# ESP-Grow_OLED_Rev_A.net
KiCad netlist of a schematic drawn in Altium Designer
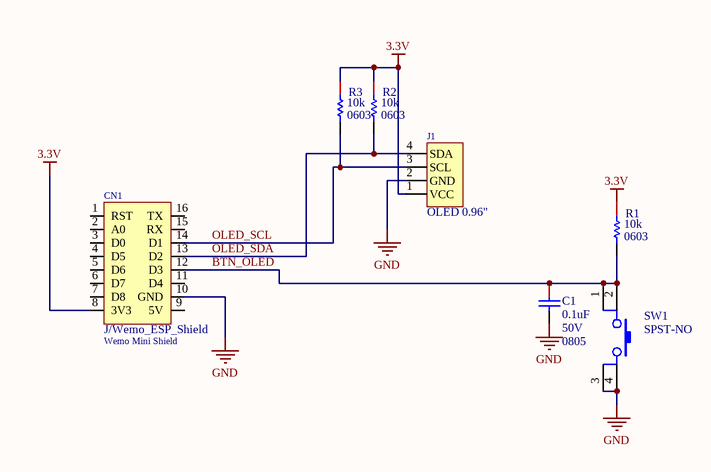
[diagram p0: ESP-Grow_OLED_Rev_A.SchDoc]

(export (version "E")
  (design (tool "Eeschema 10.0.6"))
  (components
    (comp (ref "C1")
      (value "0.1uF")
      (footprint "CAPC0805(2012)_L")
      (description "CAP CER 0.1UF 50V 10% X7R 0805")
      (fields
        (field (name "VOLTAGE (RATED)") "50V")
        (field (name "PACKAGE (IMPERIAL)") "0805")
        (field (name "TOLERANCE") "10%")
      )
      (libsource (lib "OLogic Nexus Vault") (part "=Capacitance"))
    )
    (comp (ref "CN1")
      (value "J/Wemo_ESP_Shield")
      (footprint "Wemos_d1")
      (description "Wemo Mini Shield for ESP-12")
      (fields (field (name "NAME") "Wemo Mini Shield"))
      (libsource (lib "Kyle_Lib_04-20-19") (part "J/Wemo_ESP_Shield"))
    )
    (comp (ref "J1")
      (value "OLED 0.96\"")
      (footprint "OLED_0.96_I2C")
      (description "SSD1306 I2C OLED 0.96\"")
      (libsource (lib "Kyle_Lib_04-20-19") (part "OLED_0.96_I2C"))
    )
    (comp (ref "R1")
      (value "10K")
      (footprint "RESC0603(1608)_M")
      (description "RES 10K OHM 1/10W 1% 0603 SMD")
      (fields
        (field (name "PACKAGE (IMPERIAL)") "0603")
        (field (name "RESISTANCE") "10k")
        (field (name "POWER") "100mW")
        (field (name "TOLERANCE") "1%")
      )
      (libsource (lib "OLogic Nexus Vault") (part "=Resistance"))
    )
    (comp (ref "R2")
      (value "10K")
      (footprint "RESC0603(1608)_M")
      (description "RES 10K OHM 1/10W 1% 0603 SMD")
      (fields
        (field (name "PACKAGE (IMPERIAL)") "0603")
        (field (name "RESISTANCE") "10k")
        (field (name "POWER") "100mW")
        (field (name "TOLERANCE") "1%")
      )
      (libsource (lib "OLogic Nexus Vault") (part "=Resistance"))
    )
    (comp (ref "R3")
      (value "10K")
      (footprint "RESC0603(1608)_M")
      (description "RES 10K OHM 1/10W 1% 0603 SMD")
      (fields
        (field (name "PACKAGE (IMPERIAL)") "0603")
        (field (name "RESISTANCE") "10k")
        (field (name "POWER") "100mW")
        (field (name "TOLERANCE") "1%")
      )
      (libsource (lib "OLogic Nexus Vault") (part "=Resistance"))
    )
    (comp (ref "SW1")
      (value "PTS645SM43SMTR92 LFS")
      (footprint "SW TACT Red 6mm x 6mm")
      (description "SWITCH TACTILE SPST-NO 0.05A 12V")
      (fields (field (name "CIRCUIT") "SPST-NO") (field (name "MANUFACTURER") "C&K"))
      (libsource (lib "altium-import") (part "root_0_PTS645SM43SMTR92 LFS_"))
    )
  )
  (nets
    (net (code "1") (name "/BTN_OLED") (class "Default")
      (node (ref "C1") (pin "1") (pinfunction "1_1") (pintype "passive"))
      (node (ref "CN1") (pin "12") (pinfunction "D3_12") (pintype "power_in"))
      (node (ref "R1") (pin "2") (pinfunction "2_2") (pintype "passive"))
      (node (ref "SW1") (pin "1") (pinfunction "1_1") (pintype "passive"))
      (node (ref "SW1") (pin "2") (pinfunction "2_2") (pintype "passive"))
    )
    (net (code "2") (name "/OLED_SCL") (class "Default")
      (node (ref "CN1") (pin "14") (pinfunction "D1_14") (pintype "power_in"))
      (node (ref "J1") (pin "3") (pinfunction "SCL_3") (pintype "passive"))
      (node (ref "R3") (pin "2") (pinfunction "2_2") (pintype "passive"))
    )
    (net (code "3") (name "/OLED_SDA") (class "Default")
      (node (ref "CN1") (pin "13") (pinfunction "D2_13") (pintype "power_in"))
      (node (ref "J1") (pin "4") (pinfunction "SDA_4") (pintype "passive"))
      (node (ref "R2") (pin "2") (pinfunction "2_2") (pintype "passive"))
    )
    (net (code "4") (name "3.3V") (class "Default")
      (node (ref "CN1") (pin "8") (pinfunction "3V3_8") (pintype "power_in"))
      (node (ref "J1") (pin "1") (pinfunction "VCC_1") (pintype "passive"))
      (node (ref "R1") (pin "1") (pinfunction "1_1") (pintype "passive"))
      (node (ref "R2") (pin "1") (pinfunction "1_1") (pintype "passive"))
      (node (ref "R3") (pin "1") (pinfunction "1_1") (pintype "passive"))
    )
    (net (code "5") (name "GND") (class "Default")
      (node (ref "C1") (pin "2") (pinfunction "2_2") (pintype "passive"))
      (node (ref "CN1") (pin "10") (pinfunction "GND_10") (pintype "power_in"))
      (node (ref "J1") (pin "2") (pinfunction "GND_2") (pintype "passive"))
      (node (ref "SW1") (pin "3") (pinfunction "3_3") (pintype "passive"))
      (node (ref "SW1") (pin "4") (pinfunction "4_4") (pintype "passive"))
    )
    (net (code "6") (name "unconnected-(CN1-5V-Pad9)") (class "Default")
      (node (ref "CN1") (pin "9") (pinfunction "5V_9") (pintype "power_in"))
    )
    (net (code "7") (name "unconnected-(CN1-A0-Pad2)") (class "Default")
      (node (ref "CN1") (pin "2") (pinfunction "A0_2") (pintype "power_in"))
    )
    (net (code "8") (name "unconnected-(CN1-D0-Pad3)") (class "Default")
      (node (ref "CN1") (pin "3") (pinfunction "D0_3") (pintype "power_in"))
    )
    (net (code "9") (name "unconnected-(CN1-D4-Pad11)") (class "Default")
      (node (ref "CN1") (pin "11") (pinfunction "D4_11") (pintype "power_in"))
    )
    (net (code "10") (name "unconnected-(CN1-D5-Pad4)") (class "Default")
      (node (ref "CN1") (pin "4") (pinfunction "D5_4") (pintype "power_in"))
    )
    (net (code "11") (name "unconnected-(CN1-D6-Pad5)") (class "Default")
      (node (ref "CN1") (pin "5") (pinfunction "D6_5") (pintype "power_in"))
    )
    (net (code "12") (name "unconnected-(CN1-D7-Pad6)") (class "Default")
      (node (ref "CN1") (pin "6") (pinfunction "D7_6") (pintype "power_in"))
    )
    (net (code "13") (name "unconnected-(CN1-D8-Pad7)") (class "Default")
      (node (ref "CN1") (pin "7") (pinfunction "D8_7") (pintype "power_in"))
    )
    (net (code "14") (name "unconnected-(CN1-RST-Pad1)") (class "Default")
      (node (ref "CN1") (pin "1") (pinfunction "RST_1") (pintype "power_in"))
    )
    (net (code "15") (name "unconnected-(CN1-RX-Pad15)") (class "Default")
      (node (ref "CN1") (pin "15") (pinfunction "RX_15") (pintype "power_in"))
    )
    (net (code "16") (name "unconnected-(CN1-TX-Pad16)") (class "Default")
      (node (ref "CN1") (pin "16") (pinfunction "TX_16") (pintype "power_in"))
    )
  )
)
